# Power.net
KiCad netlist of a schematic drawn in Altium Designer
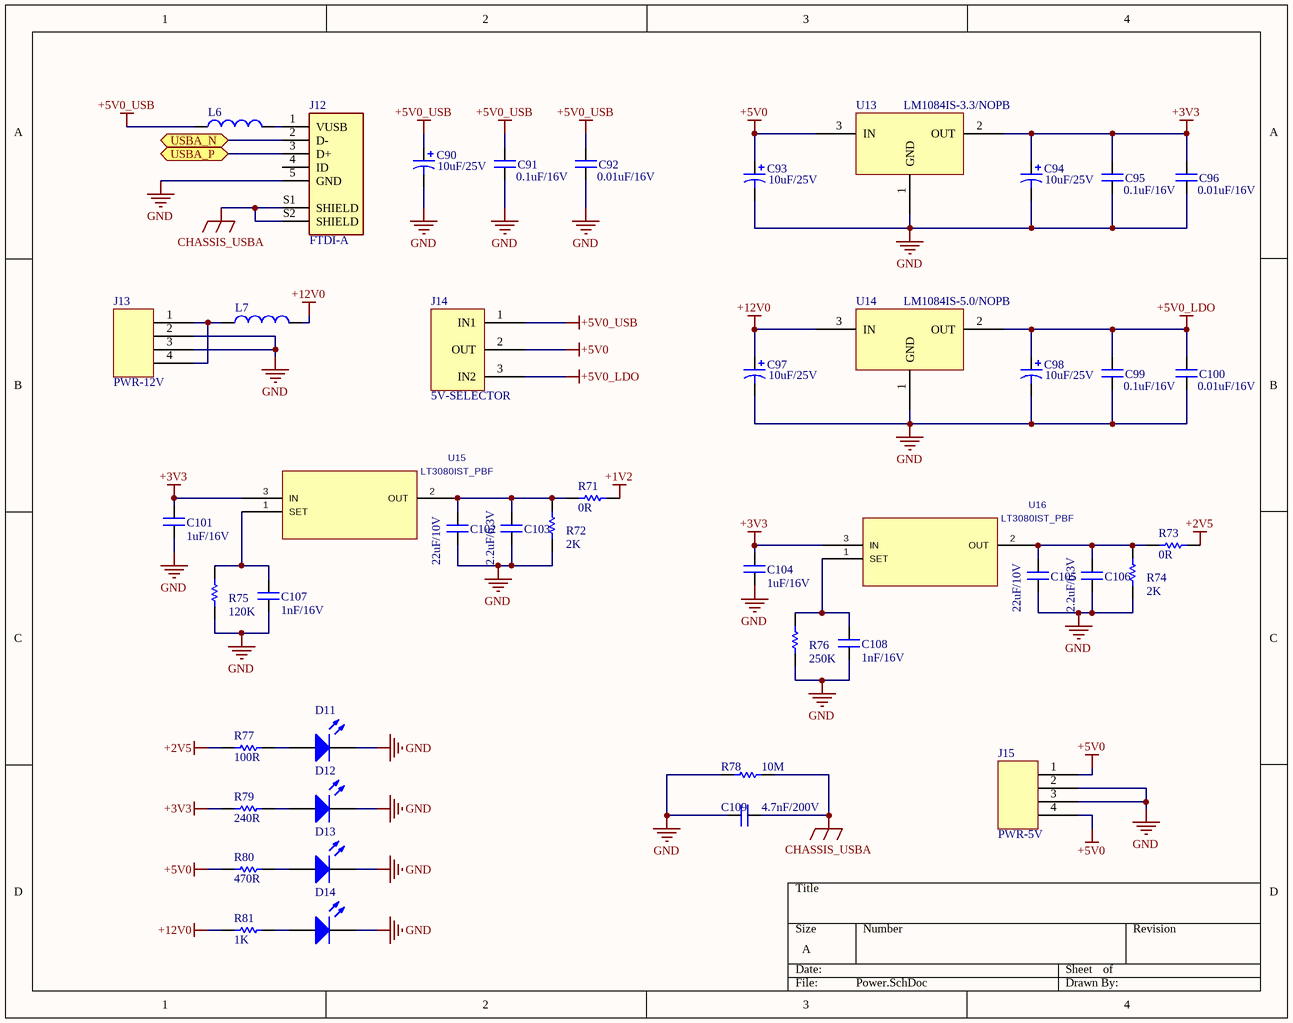
[diagram p0: Power.SchDoc]

(export (version "E")
  (design (tool "Eeschema 10.0.6"))
  (components
    (comp (ref "C90")
      (value "10uF/25V")
      (footprint "CASE-C")
      (fields (field (name "Comment") "CASE-C"))
      (libsource (lib "AdapterLib") (part "CASE-C"))
    )
    (comp (ref "C91")
      (value "0.1uF/16V")
      (footprint "CAP_0805")
      (fields (field (name "Comment") "CAP_0805"))
      (libsource (lib "AdapterLib") (part "CAP_0805"))
    )
    (comp (ref "C92")
      (value "0.01uF/16V")
      (footprint "CAP_0805")
      (fields (field (name "Comment") "CAP_0805"))
      (libsource (lib "AdapterLib") (part "CAP_0805"))
    )
    (comp (ref "C93")
      (value "10uF/25V")
      (footprint "CASE-C")
      (fields (field (name "Comment") "CASE-C"))
      (libsource (lib "AdapterLib") (part "CASE-C"))
    )
    (comp (ref "C94")
      (value "10uF/25V")
      (footprint "CASE-C")
      (fields (field (name "Comment") "CASE-C"))
      (libsource (lib "AdapterLib") (part "CASE-C"))
    )
    (comp (ref "C95")
      (value "0.1uF/16V")
      (footprint "CAP_0805")
      (fields (field (name "Comment") "CAP_0805"))
      (libsource (lib "AdapterLib") (part "CAP_0805"))
    )
    (comp (ref "C96")
      (value "0.01uF/16V")
      (footprint "CAP_0805")
      (fields (field (name "Comment") "CAP_0805"))
      (libsource (lib "AdapterLib") (part "CAP_0805"))
    )
    (comp (ref "C97")
      (value "10uF/25V")
      (footprint "CASE-C")
      (fields (field (name "Comment") "CASE-C"))
      (libsource (lib "AdapterLib") (part "CASE-C"))
    )
    (comp (ref "C98")
      (value "10uF/25V")
      (footprint "CASE-C")
      (fields (field (name "Comment") "CASE-C"))
      (libsource (lib "AdapterLib") (part "CASE-C"))
    )
    (comp (ref "C99")
      (value "0.1uF/16V")
      (footprint "CAP_0805")
      (fields (field (name "Comment") "CAP_0805"))
      (libsource (lib "AdapterLib") (part "CAP_0805"))
    )
    (comp (ref "C100")
      (value "0.01uF/16V")
      (footprint "CAP_0805")
      (fields (field (name "Comment") "CAP_0805"))
      (libsource (lib "AdapterLib") (part "CAP_0805"))
    )
    (comp (ref "C101")
      (value "1uF/16V")
      (footprint "CAP_0805")
      (fields (field (name "Comment") "CAP_0805"))
      (libsource (lib "AdapterLib") (part "CAP_0805"))
    )
    (comp (ref "C102")
      (value "22uF/10V")
      (footprint "CAP_0805")
      (fields (field (name "Comment") "CAP_0805"))
      (libsource (lib "AdapterLib") (part "CAP_0805"))
    )
    (comp (ref "C103")
      (value "2.2uF/6.3V")
      (footprint "CAP_0805")
      (fields (field (name "Comment") "CAP_0805"))
      (libsource (lib "AdapterLib") (part "CAP_0805"))
    )
    (comp (ref "C104")
      (value "1uF/16V")
      (footprint "CAP_0805")
      (fields (field (name "Comment") "CAP_0805"))
      (libsource (lib "AdapterLib") (part "CAP_0805"))
    )
    (comp (ref "C105")
      (value "22uF/10V")
      (footprint "CAP_0805")
      (fields (field (name "Comment") "CAP_0805"))
      (libsource (lib "AdapterLib") (part "CAP_0805"))
    )
    (comp (ref "C106")
      (value "2.2uF/6.3V")
      (footprint "CAP_0805")
      (fields (field (name "Comment") "CAP_0805"))
      (libsource (lib "AdapterLib") (part "CAP_0805"))
    )
    (comp (ref "C107")
      (value "1nF/16V")
      (footprint "CAP_0805")
      (fields (field (name "Comment") "CAP_0805"))
      (libsource (lib "AdapterLib") (part "CAP_0805"))
    )
    (comp (ref "C108")
      (value "1nF/16V")
      (footprint "CAP_0805")
      (fields (field (name "Comment") "CAP_0805"))
      (libsource (lib "AdapterLib") (part "CAP_0805"))
    )
    (comp (ref "C109")
      (value "4.7nF/200V")
      (footprint "CAP_0805")
      (fields (field (name "Comment") "CAP_0805"))
      (libsource (lib "AdapterLib") (part "CAP_0805"))
    )
    (comp (ref "D11")
      (value "LED_0603")
      (footprint "LED_0603")
      (libsource (lib "AdapterLib") (part "LED_0603"))
    )
    (comp (ref "D12")
      (value "LED_0603")
      (footprint "LED_0603")
      (libsource (lib "AdapterLib") (part "LED_0603"))
    )
    (comp (ref "D13")
      (value "LED_0603")
      (footprint "LED_0603")
      (libsource (lib "AdapterLib") (part "LED_0603"))
    )
    (comp (ref "D14")
      (value "LED_0603")
      (footprint "LED_0603")
      (libsource (lib "AdapterLib") (part "LED_0603"))
    )
    (comp (ref "J12")
      (value "FTDI-A")
      (footprint "UX60-MB-5S8")
      (description "USB MINI TYPE B")
      (libsource (lib "AdapterLib") (part "UX60-MB-5S8"))
    )
    (comp (ref "J13")
      (value "PWR-12V")
      (footprint "HEADER_4")
      (libsource (lib "AdapterLib") (part "HEADER_4"))
    )
    (comp (ref "J14")
      (value "5V-SELECTOR")
      (footprint "JUMPER 3 PIN")
      (description "JUMPER 3 PIN")
      (libsource (lib "AdapterLib") (part "JUMPER 3 PIN"))
    )
    (comp (ref "J15")
      (value "PWR-5V")
      (footprint "HEADER_4")
      (libsource (lib "AdapterLib") (part "HEADER_4"))
    )
    (comp (ref "L6")
      (value "IND_0805")
      (footprint "IND_0805")
      (libsource (lib "AdapterLib") (part "IND_0805"))
    )
    (comp (ref "L7")
      (value "IND_0805")
      (footprint "IND_0805")
      (libsource (lib "AdapterLib") (part "IND_0805"))
    )
    (comp (ref "R71")
      (value "0R")
      (footprint "RES_0805")
      (fields (field (name "Comment") "RES_0805"))
      (libsource (lib "AdapterLib") (part "RES_0805"))
    )
    (comp (ref "R72")
      (value "2K")
      (footprint "RES_0805")
      (fields (field (name "Comment") "RES_0805"))
      (libsource (lib "AdapterLib") (part "RES_0805"))
    )
    (comp (ref "R73")
      (value "0R")
      (footprint "RES_0805")
      (fields (field (name "Comment") "RES_0805"))
      (libsource (lib "AdapterLib") (part "RES_0805"))
    )
    (comp (ref "R74")
      (value "2K")
      (footprint "RES_0805")
      (fields (field (name "Comment") "RES_0805"))
      (libsource (lib "AdapterLib") (part "RES_0805"))
    )
    (comp (ref "R75")
      (value "120K")
      (footprint "RES_0805")
      (fields (field (name "Comment") "RES_0805"))
      (libsource (lib "AdapterLib") (part "RES_0805"))
    )
    (comp (ref "R76")
      (value "250K")
      (footprint "RES_0805")
      (fields (field (name "Comment") "RES_0805"))
      (libsource (lib "AdapterLib") (part "RES_0805"))
    )
    (comp (ref "R77")
      (value "100R")
      (footprint "RES_0805")
      (fields (field (name "Comment") "RES_0805"))
      (libsource (lib "AdapterLib") (part "RES_0805"))
    )
    (comp (ref "R78")
      (value "10M")
      (footprint "RES_0805")
      (fields (field (name "Comment") "RES_0805"))
      (libsource (lib "AdapterLib") (part "RES_0805"))
    )
    (comp (ref "R79")
      (value "240R")
      (footprint "RES_0805")
      (fields (field (name "Comment") "RES_0805"))
      (libsource (lib "AdapterLib") (part "RES_0805"))
    )
    (comp (ref "R80")
      (value "470R")
      (footprint "RES_0805")
      (fields (field (name "Comment") "RES_0805"))
      (libsource (lib "AdapterLib") (part "RES_0805"))
    )
    (comp (ref "R81")
      (value "1K")
      (footprint "RES_0805")
      (fields (field (name "Comment") "RES_0805"))
      (libsource (lib "AdapterLib") (part "RES_0805"))
    )
    (comp (ref "U13")
      (value "LM1084IS-3.3/NOPB")
      (footprint "LM1084IS-3.3/NOPB")
      (libsource (lib "AdapterLib") (part "LM1084IS-3.3/NOPB"))
    )
    (comp (ref "U14")
      (value "LM1084IS-5.0/NOPB")
      (footprint "LM1084IS-5.0/NOPB")
      (libsource (lib "AdapterLib") (part "LM1084IS-5.0/NOPB"))
    )
    (comp (ref "U15")
      (value "LT3080IST_PBF")
      (footprint "LT3080IST_PBF")
      (fields (field (name "MANUFACTURER_PART_NUMBER") "LT3080IST#PBF"))
      (libsource (lib "AdapterLib") (part "LT3080IST_PBF"))
    )
    (comp (ref "U16")
      (value "LT3080IST_PBF")
      (footprint "LT3080IST_PBF")
      (fields (field (name "MANUFACTURER_PART_NUMBER") "LT3080IST#PBF"))
      (libsource (lib "AdapterLib") (part "LT3080IST_PBF"))
    )
  )
  (nets
    (net (code "1") (name "+1V2") (class "Default")
      (node (ref "R71") (pin "1") (pinfunction "1_1") (pintype "passive"))
    )
    (net (code "2") (name "+2V5") (class "Default")
      (node (ref "R73") (pin "1") (pinfunction "1_1") (pintype "passive"))
      (node (ref "R77") (pin "1") (pinfunction "1_1") (pintype "passive"))
    )
    (net (code "3") (name "+3V3") (class "Default")
      (node (ref "C101") (pin "2") (pinfunction "2_2") (pintype "passive"))
      (node (ref "C104") (pin "2") (pinfunction "2_2") (pintype "passive"))
      (node (ref "C94") (pin "A") (pinfunction "1_A") (pintype "passive"))
      (node (ref "C95") (pin "2") (pinfunction "2_2") (pintype "passive"))
      (node (ref "C96") (pin "2") (pinfunction "2_2") (pintype "passive"))
      (node (ref "R79") (pin "1") (pinfunction "1_1") (pintype "passive"))
      (node (ref "U13") (pin "2") (pinfunction "OUT_2") (pintype "passive"))
      (node (ref "U15") (pin "3") (pinfunction "IN_3") (pintype "passive"))
      (node (ref "U16") (pin "3") (pinfunction "IN_3") (pintype "passive"))
    )
    (net (code "4") (name "+5V0") (class "Default")
      (node (ref "C93") (pin "A") (pinfunction "1_A") (pintype "passive"))
      (node (ref "J14") (pin "2") (pinfunction "OUT_2") (pintype "passive"))
      (node (ref "J15") (pin "1") (pintype "passive"))
      (node (ref "J15") (pin "4") (pintype "passive"))
      (node (ref "R80") (pin "1") (pinfunction "1_1") (pintype "passive"))
      (node (ref "U13") (pin "3") (pinfunction "IN_3") (pintype "passive"))
    )
    (net (code "5") (name "+5V0_LDO") (class "Default")
      (node (ref "C100") (pin "2") (pinfunction "2_2") (pintype "passive"))
      (node (ref "C98") (pin "A") (pinfunction "1_A") (pintype "passive"))
      (node (ref "C99") (pin "2") (pinfunction "2_2") (pintype "passive"))
      (node (ref "J14") (pin "3") (pinfunction "IN2_3") (pintype "passive"))
      (node (ref "U14") (pin "2") (pinfunction "OUT_2") (pintype "passive"))
    )
    (net (code "6") (name "+5V0_USB") (class "Default")
      (node (ref "C90") (pin "A") (pinfunction "1_A") (pintype "passive"))
      (node (ref "C91") (pin "2") (pinfunction "2_2") (pintype "passive"))
      (node (ref "C92") (pin "2") (pinfunction "2_2") (pintype "passive"))
      (node (ref "J14") (pin "1") (pinfunction "IN1_1") (pintype "passive"))
      (node (ref "L6") (pin "1") (pinfunction "1_1") (pintype "passive"))
    )
    (net (code "7") (name "+12V0") (class "Default")
      (node (ref "C97") (pin "A") (pinfunction "1_A") (pintype "passive"))
      (node (ref "L7") (pin "2") (pinfunction "2_2") (pintype "passive"))
      (node (ref "R81") (pin "1") (pinfunction "1_1") (pintype "passive"))
      (node (ref "U14") (pin "3") (pinfunction "IN_3") (pintype "passive"))
    )
    (net (code "8") (name "/USBA_N") (class "Default")
      (node (ref "J12") (pin "2") (pinfunction "D-_2") (pintype "passive"))
    )
    (net (code "9") (name "/USBA_P") (class "Default")
      (node (ref "J12") (pin "3") (pinfunction "D+_3") (pintype "passive"))
    )
    (net (code "10") (name "CHASSIS_USBA") (class "Default")
      (node (ref "C109") (pin "1") (pinfunction "1_1") (pintype "passive"))
      (node (ref "J12") (pin "S1") (pinfunction "SHIELD_S1") (pintype "passive"))
      (node (ref "J12") (pin "S2") (pinfunction "SHIELD_S2") (pintype "passive"))
      (node (ref "R78") (pin "1") (pinfunction "1_1") (pintype "passive"))
    )
    (net (code "11") (name "GND") (class "Default")
      (node (ref "C100") (pin "1") (pinfunction "1_1") (pintype "passive"))
      (node (ref "C101") (pin "1") (pinfunction "1_1") (pintype "passive"))
      (node (ref "C102") (pin "1") (pinfunction "1_1") (pintype "passive"))
      (node (ref "C103") (pin "1") (pinfunction "1_1") (pintype "passive"))
      (node (ref "C104") (pin "1") (pinfunction "1_1") (pintype "passive"))
      (node (ref "C105") (pin "1") (pinfunction "1_1") (pintype "passive"))
      (node (ref "C106") (pin "1") (pinfunction "1_1") (pintype "passive"))
      (node (ref "C107") (pin "1") (pinfunction "1_1") (pintype "passive"))
      (node (ref "C108") (pin "1") (pinfunction "1_1") (pintype "passive"))
      (node (ref "C109") (pin "2") (pinfunction "2_2") (pintype "passive"))
      (node (ref "C90") (pin "K") (pinfunction "2_K") (pintype "passive"))
      (node (ref "C91") (pin "1") (pinfunction "1_1") (pintype "passive"))
      (node (ref "C92") (pin "1") (pinfunction "1_1") (pintype "passive"))
      (node (ref "C93") (pin "K") (pinfunction "2_K") (pintype "passive"))
      (node (ref "C94") (pin "K") (pinfunction "2_K") (pintype "passive"))
      (node (ref "C95") (pin "1") (pinfunction "1_1") (pintype "passive"))
      (node (ref "C96") (pin "1") (pinfunction "1_1") (pintype "passive"))
      (node (ref "C97") (pin "K") (pinfunction "2_K") (pintype "passive"))
      (node (ref "C98") (pin "K") (pinfunction "2_K") (pintype "passive"))
      (node (ref "C99") (pin "1") (pinfunction "1_1") (pintype "passive"))
      (node (ref "D11") (pin "2") (pinfunction "K_2") (pintype "passive"))
      (node (ref "D12") (pin "2") (pinfunction "K_2") (pintype "passive"))
      (node (ref "D13") (pin "2") (pinfunction "K_2") (pintype "passive"))
      (node (ref "D14") (pin "2") (pinfunction "K_2") (pintype "passive"))
      (node (ref "J12") (pin "5") (pinfunction "GND_5") (pintype "passive"))
      (node (ref "J13") (pin "2") (pintype "passive"))
      (node (ref "J13") (pin "3") (pintype "passive"))
      (node (ref "J15") (pin "2") (pintype "passive"))
      (node (ref "J15") (pin "3") (pintype "passive"))
      (node (ref "R72") (pin "1") (pinfunction "1_1") (pintype "passive"))
      (node (ref "R74") (pin "1") (pinfunction "1_1") (pintype "passive"))
      (node (ref "R75") (pin "1") (pinfunction "1_1") (pintype "passive"))
      (node (ref "R76") (pin "1") (pinfunction "1_1") (pintype "passive"))
      (node (ref "R78") (pin "2") (pinfunction "2_2") (pintype "passive"))
      (node (ref "U13") (pin "1") (pinfunction "GND_1") (pintype "passive"))
      (node (ref "U14") (pin "1") (pinfunction "GND_1") (pintype "passive"))
    )
    (net (code "12") (name "Net-(D11-A)") (class "Default")
      (node (ref "D11") (pin "1") (pinfunction "A_1") (pintype "passive"))
      (node (ref "R77") (pin "2") (pinfunction "2_2") (pintype "passive"))
    )
    (net (code "13") (name "Net-(D12-A)") (class "Default")
      (node (ref "D12") (pin "1") (pinfunction "A_1") (pintype "passive"))
      (node (ref "R79") (pin "2") (pinfunction "2_2") (pintype "passive"))
    )
    (net (code "14") (name "Net-(D13-A)") (class "Default")
      (node (ref "D13") (pin "1") (pinfunction "A_1") (pintype "passive"))
      (node (ref "R80") (pin "2") (pinfunction "2_2") (pintype "passive"))
    )
    (net (code "15") (name "Net-(D14-A)") (class "Default")
      (node (ref "D14") (pin "1") (pinfunction "A_1") (pintype "passive"))
      (node (ref "R81") (pin "2") (pinfunction "2_2") (pintype "passive"))
    )
    (net (code "16") (name "Net-(J12-VUSB)") (class "Default")
      (node (ref "J12") (pin "1") (pinfunction "VUSB_1") (pintype "passive"))
      (node (ref "L6") (pin "2") (pinfunction "2_2") (pintype "passive"))
    )
    (net (code "17") (name "Net-(J13-Pad1)") (class "Default")
      (node (ref "J13") (pin "1") (pintype "passive"))
      (node (ref "J13") (pin "4") (pintype "passive"))
      (node (ref "L7") (pin "1") (pinfunction "1_1") (pintype "passive"))
    )
    (net (code "18") (name "Net-(U15-OUT)") (class "Default")
      (node (ref "C102") (pin "2") (pinfunction "2_2") (pintype "passive"))
      (node (ref "C103") (pin "2") (pinfunction "2_2") (pintype "passive"))
      (node (ref "R71") (pin "2") (pinfunction "2_2") (pintype "passive"))
      (node (ref "R72") (pin "2") (pinfunction "2_2") (pintype "passive"))
      (node (ref "U15") (pin "2") (pinfunction "OUT_2") (pintype "passive"))
    )
    (net (code "19") (name "Net-(U15-SET)") (class "Default")
      (node (ref "C107") (pin "2") (pinfunction "2_2") (pintype "passive"))
      (node (ref "R75") (pin "2") (pinfunction "2_2") (pintype "passive"))
      (node (ref "U15") (pin "1") (pinfunction "SET_1") (pintype "passive"))
    )
    (net (code "20") (name "Net-(U16-OUT)") (class "Default")
      (node (ref "C105") (pin "2") (pinfunction "2_2") (pintype "passive"))
      (node (ref "C106") (pin "2") (pinfunction "2_2") (pintype "passive"))
      (node (ref "R73") (pin "2") (pinfunction "2_2") (pintype "passive"))
      (node (ref "R74") (pin "2") (pinfunction "2_2") (pintype "passive"))
      (node (ref "U16") (pin "2") (pinfunction "OUT_2") (pintype "passive"))
    )
    (net (code "21") (name "Net-(U16-SET)") (class "Default")
      (node (ref "C108") (pin "2") (pinfunction "2_2") (pintype "passive"))
      (node (ref "R76") (pin "2") (pinfunction "2_2") (pintype "passive"))
      (node (ref "U16") (pin "1") (pinfunction "SET_1") (pintype "passive"))
    )
    (net (code "22") (name "unconnected-(J12-ID-Pad4)") (class "Default")
      (node (ref "J12") (pin "4") (pinfunction "ID_4") (pintype "passive"))
    )
  )
)
